# InputAnalog.net
KiCad netlist of a schematic drawn in Altium Designer
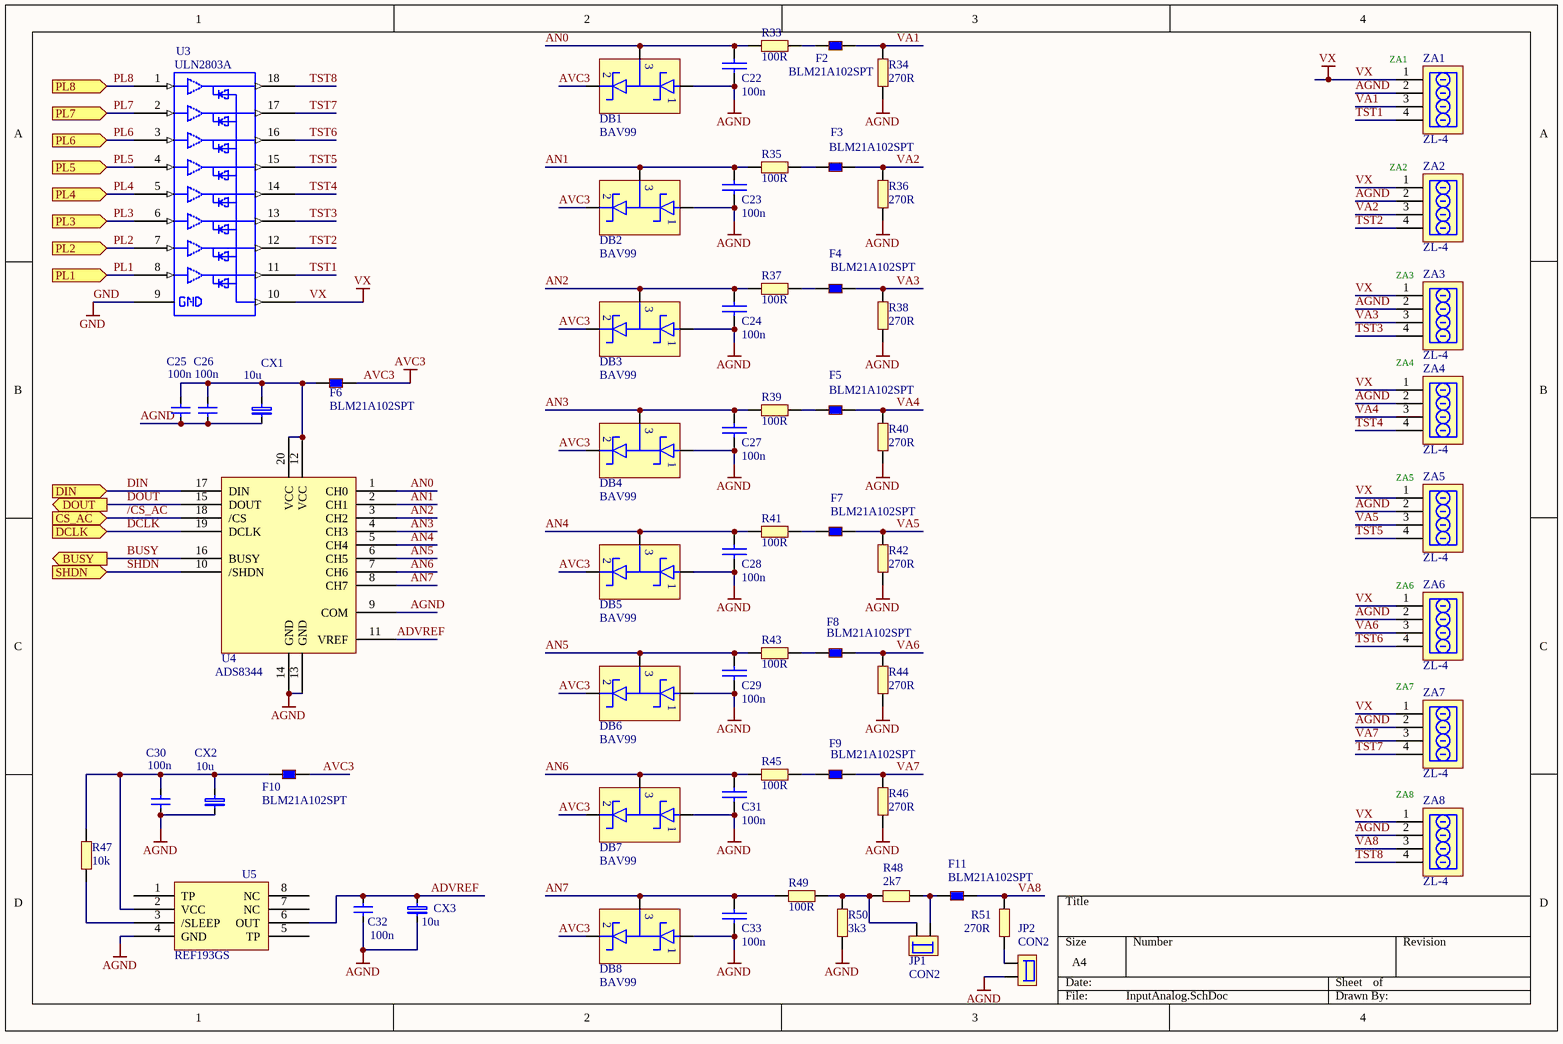
[diagram p0: InputAnalog.SchDoc]

(export (version "E")
  (design (tool "Eeschema 10.0.6"))
  (components
    (comp (ref "C22")
      (value "100n")
      (footprint "0603C")
      (description "Capacitor")
      (libsource (lib "*") (part "CAP"))
    )
    (comp (ref "C23")
      (value "100n")
      (footprint "0603C")
      (description "Capacitor")
      (libsource (lib "*") (part "CAP"))
    )
    (comp (ref "C24")
      (value "100n")
      (footprint "0603C")
      (description "Capacitor")
      (libsource (lib "*") (part "CAP"))
    )
    (comp (ref "C25") (value "100n") (footprint "0603C") (libsource (lib "") (part "CAP_1")))
    (comp (ref "C26") (value "100n") (footprint "0603C") (libsource (lib "") (part "CAP_1")))
    (comp (ref "C27")
      (value "100n")
      (footprint "0603C")
      (description "Capacitor")
      (libsource (lib "*") (part "CAP"))
    )
    (comp (ref "C28")
      (value "100n")
      (footprint "0603C")
      (description "Capacitor")
      (libsource (lib "*") (part "CAP"))
    )
    (comp (ref "C29")
      (value "100n")
      (footprint "0603C")
      (description "Capacitor")
      (libsource (lib "*") (part "CAP"))
    )
    (comp (ref "C30") (value "100n") (footprint "0603C") (libsource (lib "") (part "CAP_1")))
    (comp (ref "C31")
      (value "100n")
      (footprint "0603C")
      (description "Capacitor")
      (libsource (lib "*") (part "CAP"))
    )
    (comp (ref "C32") (value "100n") (footprint "0603C") (libsource (lib "") (part "CAP_1")))
    (comp (ref "C33")
      (value "100n")
      (footprint "0603C")
      (description "Capacitor")
      (libsource (lib "*") (part "CAP"))
    )
    (comp (ref "CX1")
      (value "10u")
      (footprint "CAP_A")
      (description "KONDENSATOR ELEKTROLITYCZNY TANTALOWY SMD")
      (libsource (lib "*") (part "CAP_TANTAL_SMD"))
    )
    (comp (ref "CX2")
      (value "10u")
      (footprint "CAP_A")
      (description "KONDENSATOR ELEKTROLITYCZNY TANTALOWY SMD")
      (libsource (lib "*") (part "CAP_TANTAL_SMD"))
    )
    (comp (ref "CX3")
      (value "10u")
      (footprint "CAP_A")
      (description "KONDENSATOR ELEKTROLITYCZNY TANTALOWY SMD")
      (libsource (lib "*") (part "CAP_TANTAL_SMD"))
    )
    (comp (ref "DB1") (value "BAV99") (footprint "SOT-23") (libsource (lib "*") (part "BAS70-04")))
    (comp (ref "DB2") (value "BAV99") (footprint "SOT-23") (libsource (lib "*") (part "BAS70-04")))
    (comp (ref "DB3") (value "BAV99") (footprint "SOT-23") (libsource (lib "*") (part "BAS70-04")))
    (comp (ref "DB4") (value "BAV99") (footprint "SOT-23") (libsource (lib "*") (part "BAS70-04")))
    (comp (ref "DB5") (value "BAV99") (footprint "SOT-23") (libsource (lib "*") (part "BAS70-04")))
    (comp (ref "DB6") (value "BAV99") (footprint "SOT-23") (libsource (lib "*") (part "BAS70-04")))
    (comp (ref "DB7") (value "BAV99") (footprint "SOT-23") (libsource (lib "*") (part "BAS70-04")))
    (comp (ref "DB8") (value "BAV99") (footprint "SOT-23") (libsource (lib "*") (part "BAS70-04")))
    (comp (ref "F2")
      (value "BLM21A102SPT")
      (footprint "0603L")
      (description "Koralik ferrytowy")
      (libsource (lib "*") (part "KORALIK"))
    )
    (comp (ref "F3")
      (value "BLM21A102SPT")
      (footprint "0603L")
      (description "Koralik ferrytowy")
      (libsource (lib "*") (part "KORALIK"))
    )
    (comp (ref "F4")
      (value "BLM21A102SPT")
      (footprint "0603L")
      (description "Koralik ferrytowy")
      (libsource (lib "*") (part "KORALIK"))
    )
    (comp (ref "F5")
      (value "BLM21A102SPT")
      (footprint "0603L")
      (description "Koralik ferrytowy")
      (libsource (lib "*") (part "KORALIK"))
    )
    (comp (ref "F6")
      (value "BLM21A102SPT")
      (footprint "0603L")
      (description "Koralik ferrytowy")
      (libsource (lib "*") (part "KORALIK"))
    )
    (comp (ref "F7")
      (value "BLM21A102SPT")
      (footprint "0603L")
      (description "Koralik ferrytowy")
      (libsource (lib "*") (part "KORALIK"))
    )
    (comp (ref "F8")
      (value "BLM21A102SPT")
      (footprint "0603L")
      (description "Koralik ferrytowy")
      (libsource (lib "*") (part "KORALIK"))
    )
    (comp (ref "F9")
      (value "BLM21A102SPT")
      (footprint "0603L")
      (description "Koralik ferrytowy")
      (libsource (lib "*") (part "KORALIK"))
    )
    (comp (ref "F10")
      (value "BLM21A102SPT")
      (footprint "0603L")
      (description "Koralik ferrytowy")
      (libsource (lib "*") (part "KORALIK"))
    )
    (comp (ref "F11")
      (value "BLM21A102SPT")
      (footprint "0603L")
      (description "Koralik ferrytowy")
      (libsource (lib "*") (part "KORALIK"))
    )
    (comp (ref "JP1")
      (value "CON2")
      (footprint "SIP2")
      (description "Connector")
      (libsource (lib "ElhosSchLib") (part "JUMP2"))
    )
    (comp (ref "JP2")
      (value "CON2")
      (footprint "SIP2")
      (description "Connector")
      (libsource (lib "") (part "JUMP2_1"))
    )
    (comp (ref "R33") (value "100R") (footprint "0603R") (libsource (lib "*") (part "RES3")))
    (comp (ref "R34") (value "270R") (footprint "0805R") (libsource (lib "") (part "RES3_1")))
    (comp (ref "R35") (value "100R") (footprint "0603R") (libsource (lib "*") (part "RES3")))
    (comp (ref "R36") (value "270R") (footprint "0805R") (libsource (lib "") (part "RES3_1")))
    (comp (ref "R37") (value "100R") (footprint "0603R") (libsource (lib "*") (part "RES3")))
    (comp (ref "R38") (value "270R") (footprint "0805R") (libsource (lib "") (part "RES3_1")))
    (comp (ref "R39") (value "100R") (footprint "0603R") (libsource (lib "*") (part "RES3")))
    (comp (ref "R40") (value "270R") (footprint "0805R") (libsource (lib "") (part "RES3_1")))
    (comp (ref "R41") (value "100R") (footprint "0603R") (libsource (lib "*") (part "RES3")))
    (comp (ref "R42") (value "270R") (footprint "0805R") (libsource (lib "") (part "RES3_1")))
    (comp (ref "R43") (value "100R") (footprint "0603R") (libsource (lib "*") (part "RES3")))
    (comp (ref "R44") (value "270R") (footprint "0805R") (libsource (lib "") (part "RES3_1")))
    (comp (ref "R45") (value "100R") (footprint "0603R") (libsource (lib "*") (part "RES3")))
    (comp (ref "R46") (value "270R") (footprint "0805R") (libsource (lib "") (part "RES3_1")))
    (comp (ref "R47") (value "10k") (footprint "0603R") (libsource (lib "*") (part "RES3")))
    (comp (ref "R48") (value "2k7") (footprint "0603R") (libsource (lib "*") (part "RES3")))
    (comp (ref "R49") (value "100R") (footprint "0603R") (libsource (lib "*") (part "RES3")))
    (comp (ref "R50") (value "3k3") (footprint "0603R") (libsource (lib "") (part "RES3_2")))
    (comp (ref "R51") (value "270R") (footprint "0805R") (libsource (lib "") (part "RES3_1")))
    (comp (ref "U3")
      (value "ULN2803A")
      (footprint "SO-18")
      (libsource (lib "*") (part "Pro31.tmp_ULN2803A_42"))
    )
    (comp (ref "U4") (value "ADS8344") (footprint "TSSOP20") (libsource (lib "*") (part "ADS8344")))
    (comp (ref "U5") (value "REF193GS") (footprint "SO8") (libsource (lib "*") (part "REF19X")))
    (comp (ref "ZA1") (value "ZL-4") (footprint "ARC-4-3.5-TYCO-2") (libsource (lib "*") (part "ZL-4")))
    (comp (ref "ZA2") (value "ZL-4") (footprint "ARC-4-3.5-TYCO-2") (libsource (lib "*") (part "ZL-4")))
    (comp (ref "ZA3") (value "ZL-4") (footprint "ARC-4-3.5-TYCO-2") (libsource (lib "*") (part "ZL-4")))
    (comp (ref "ZA4") (value "ZL-4") (footprint "ARC-4-3.5-TYCO-2") (libsource (lib "*") (part "ZL-4")))
    (comp (ref "ZA5") (value "ZL-4") (footprint "ARC-4-3.5-TYCO-2") (libsource (lib "*") (part "ZL-4")))
    (comp (ref "ZA6") (value "ZL-4") (footprint "ARC-4-3.5-TYCO-2") (libsource (lib "*") (part "ZL-4")))
    (comp (ref "ZA7") (value "ZL-4") (footprint "ARC-4-3.5-TYCO-2") (libsource (lib "*") (part "ZL-4")))
    (comp (ref "ZA8") (value "ZL-4") (footprint "ARC-4-3.5-TYCO-2") (libsource (lib "*") (part "ZL-4")))
  )
  (nets
    (net (code "1") (name "/ADVREF") (class "Default")
      (node (ref "C32") (pin "1") (pintype "passive"))
      (node (ref "CX3") (pin "2") (pintype "passive"))
      (node (ref "U4") (pin "11") (pinfunction "VREF_11") (pintype "passive"))
      (node (ref "U5") (pin "6") (pinfunction "OUT_6") (pintype "passive"))
    )
    (net (code "2") (name "/AN0") (class "Default")
      (node (ref "C22") (pin "1") (pinfunction "1_1") (pintype "passive"))
      (node (ref "DB1") (pin "3") (pintype "passive"))
      (node (ref "R33") (pin "2") (pintype "passive"))
      (node (ref "U4") (pin "1") (pinfunction "CH0_1") (pintype "passive"))
    )
    (net (code "3") (name "/AN1") (class "Default")
      (node (ref "C23") (pin "1") (pinfunction "1_1") (pintype "passive"))
      (node (ref "DB2") (pin "3") (pintype "passive"))
      (node (ref "R35") (pin "2") (pintype "passive"))
      (node (ref "U4") (pin "2") (pinfunction "CH1_2") (pintype "passive"))
    )
    (net (code "4") (name "/AN2") (class "Default")
      (node (ref "C24") (pin "1") (pinfunction "1_1") (pintype "passive"))
      (node (ref "DB3") (pin "3") (pintype "passive"))
      (node (ref "R37") (pin "2") (pintype "passive"))
      (node (ref "U4") (pin "3") (pinfunction "CH2_3") (pintype "passive"))
    )
    (net (code "5") (name "/AN3") (class "Default")
      (node (ref "C27") (pin "1") (pinfunction "1_1") (pintype "passive"))
      (node (ref "DB4") (pin "3") (pintype "passive"))
      (node (ref "R39") (pin "2") (pintype "passive"))
      (node (ref "U4") (pin "4") (pinfunction "CH3_4") (pintype "passive"))
    )
    (net (code "6") (name "/AN4") (class "Default")
      (node (ref "C28") (pin "1") (pinfunction "1_1") (pintype "passive"))
      (node (ref "DB5") (pin "3") (pintype "passive"))
      (node (ref "R41") (pin "2") (pintype "passive"))
      (node (ref "U4") (pin "5") (pinfunction "CH4_5") (pintype "passive"))
    )
    (net (code "7") (name "/AN5") (class "Default")
      (node (ref "C29") (pin "1") (pinfunction "1_1") (pintype "passive"))
      (node (ref "DB6") (pin "3") (pintype "passive"))
      (node (ref "R43") (pin "2") (pintype "passive"))
      (node (ref "U4") (pin "6") (pinfunction "CH5_6") (pintype "passive"))
    )
    (net (code "8") (name "/AN6") (class "Default")
      (node (ref "C31") (pin "1") (pinfunction "1_1") (pintype "passive"))
      (node (ref "DB7") (pin "3") (pintype "passive"))
      (node (ref "R45") (pin "2") (pintype "passive"))
      (node (ref "U4") (pin "7") (pinfunction "CH6_7") (pintype "passive"))
    )
    (net (code "9") (name "/AN7") (class "Default")
      (node (ref "C33") (pin "1") (pinfunction "1_1") (pintype "passive"))
      (node (ref "DB8") (pin "3") (pintype "passive"))
      (node (ref "R49") (pin "2") (pintype "passive"))
      (node (ref "U4") (pin "8") (pinfunction "CH7_8") (pintype "passive"))
    )
    (net (code "10") (name "/BUSY") (class "Default")
      (node (ref "U4") (pin "16") (pinfunction "BUSY_16") (pintype "passive"))
    )
    (net (code "11") (name "/DCLK") (class "Default")
      (node (ref "U4") (pin "19") (pinfunction "DCLK_19") (pintype "passive"))
    )
    (net (code "12") (name "/DIN") (class "Default")
      (node (ref "U4") (pin "17") (pinfunction "DIN_17") (pintype "passive"))
    )
    (net (code "13") (name "/DOUT") (class "Default")
      (node (ref "U4") (pin "15") (pinfunction "DOUT_15") (pintype "passive"))
    )
    (net (code "14") (name "/PL1") (class "Default") (node (ref "U3") (pin "8") (pintype "input")))
    (net (code "15") (name "/PL2") (class "Default") (node (ref "U3") (pin "7") (pintype "input")))
    (net (code "16") (name "/PL3") (class "Default") (node (ref "U3") (pin "6") (pintype "input")))
    (net (code "17") (name "/PL4") (class "Default") (node (ref "U3") (pin "5") (pintype "input")))
    (net (code "18") (name "/PL5") (class "Default") (node (ref "U3") (pin "4") (pintype "input")))
    (net (code "19") (name "/PL6") (class "Default") (node (ref "U3") (pin "3") (pintype "input")))
    (net (code "20") (name "/PL7") (class "Default") (node (ref "U3") (pin "2") (pintype "input")))
    (net (code "21") (name "/PL8") (class "Default") (node (ref "U3") (pin "1") (pintype "input")))
    (net (code "22") (name "/SHDN") (class "Default")
      (node (ref "U4") (pin "10") (pinfunction "/SHDN_10") (pintype "passive"))
    )
    (net (code "23") (name "/TST1") (class "Default")
      (node (ref "U3") (pin "11") (pintype "output"))
      (node (ref "ZA1") (pin "4") (pintype "passive"))
    )
    (net (code "24") (name "/TST2") (class "Default")
      (node (ref "U3") (pin "12") (pintype "output"))
      (node (ref "ZA2") (pin "4") (pintype "passive"))
    )
    (net (code "25") (name "/TST3") (class "Default")
      (node (ref "U3") (pin "13") (pintype "output"))
      (node (ref "ZA3") (pin "4") (pintype "passive"))
    )
    (net (code "26") (name "/TST4") (class "Default")
      (node (ref "U3") (pin "14") (pintype "output"))
      (node (ref "ZA4") (pin "4") (pintype "passive"))
    )
    (net (code "27") (name "/TST5") (class "Default")
      (node (ref "U3") (pin "15") (pintype "output"))
      (node (ref "ZA5") (pin "4") (pintype "passive"))
    )
    (net (code "28") (name "/TST6") (class "Default")
      (node (ref "U3") (pin "16") (pintype "output"))
      (node (ref "ZA6") (pin "4") (pintype "passive"))
    )
    (net (code "29") (name "/TST7") (class "Default")
      (node (ref "U3") (pin "17") (pintype "output"))
      (node (ref "ZA7") (pin "4") (pintype "passive"))
    )
    (net (code "30") (name "/TST8") (class "Default")
      (node (ref "U3") (pin "18") (pintype "output"))
      (node (ref "ZA8") (pin "4") (pintype "passive"))
    )
    (net (code "31") (name "/VA1") (class "Default")
      (node (ref "F2") (pin "2") (pintype "passive"))
      (node (ref "R34") (pin "2") (pintype "passive"))
      (node (ref "ZA1") (pin "3") (pintype "passive"))
    )
    (net (code "32") (name "/VA2") (class "Default")
      (node (ref "F3") (pin "2") (pintype "passive"))
      (node (ref "R36") (pin "2") (pintype "passive"))
      (node (ref "ZA2") (pin "3") (pintype "passive"))
    )
    (net (code "33") (name "/VA3") (class "Default")
      (node (ref "F4") (pin "2") (pintype "passive"))
      (node (ref "R38") (pin "2") (pintype "passive"))
      (node (ref "ZA3") (pin "3") (pintype "passive"))
    )
    (net (code "34") (name "/VA4") (class "Default")
      (node (ref "F5") (pin "2") (pintype "passive"))
      (node (ref "R40") (pin "2") (pintype "passive"))
      (node (ref "ZA4") (pin "3") (pintype "passive"))
    )
    (net (code "35") (name "/VA5") (class "Default")
      (node (ref "F7") (pin "2") (pintype "passive"))
      (node (ref "R42") (pin "2") (pintype "passive"))
      (node (ref "ZA5") (pin "3") (pintype "passive"))
    )
    (net (code "36") (name "/VA6") (class "Default")
      (node (ref "F8") (pin "2") (pintype "passive"))
      (node (ref "R44") (pin "2") (pintype "passive"))
      (node (ref "ZA6") (pin "3") (pintype "passive"))
    )
    (net (code "37") (name "/VA7") (class "Default")
      (node (ref "F9") (pin "2") (pintype "passive"))
      (node (ref "R46") (pin "2") (pintype "passive"))
      (node (ref "ZA7") (pin "3") (pintype "passive"))
    )
    (net (code "38") (name "/VA8") (class "Default")
      (node (ref "F11") (pin "2") (pintype "passive"))
      (node (ref "R51") (pin "2") (pintype "passive"))
      (node (ref "ZA8") (pin "3") (pintype "passive"))
    )
    (net (code "39") (name "/{slash}CS_AC") (class "Default")
      (node (ref "U4") (pin "18") (pinfunction "/CS_18") (pintype "passive"))
    )
    (net (code "40") (name "AGND") (class "Default")
      (node (ref "C22") (pin "2") (pinfunction "2_2") (pintype "passive"))
      (node (ref "C23") (pin "2") (pinfunction "2_2") (pintype "passive"))
      (node (ref "C24") (pin "2") (pinfunction "2_2") (pintype "passive"))
      (node (ref "C25") (pin "2") (pintype "passive"))
      (node (ref "C26") (pin "2") (pintype "passive"))
      (node (ref "C27") (pin "2") (pinfunction "2_2") (pintype "passive"))
      (node (ref "C28") (pin "2") (pinfunction "2_2") (pintype "passive"))
      (node (ref "C29") (pin "2") (pinfunction "2_2") (pintype "passive"))
      (node (ref "C30") (pin "2") (pintype "passive"))
      (node (ref "C31") (pin "2") (pinfunction "2_2") (pintype "passive"))
      (node (ref "C32") (pin "2") (pintype "passive"))
      (node (ref "C33") (pin "2") (pinfunction "2_2") (pintype "passive"))
      (node (ref "CX1") (pin "1") (pintype "passive"))
      (node (ref "CX2") (pin "1") (pintype "passive"))
      (node (ref "CX3") (pin "1") (pintype "passive"))
      (node (ref "DB1") (pin "1") (pintype "passive"))
      (node (ref "DB2") (pin "1") (pintype "passive"))
      (node (ref "DB3") (pin "1") (pintype "passive"))
      (node (ref "DB4") (pin "1") (pintype "passive"))
      (node (ref "DB5") (pin "1") (pintype "passive"))
      (node (ref "DB6") (pin "1") (pintype "passive"))
      (node (ref "DB7") (pin "1") (pintype "passive"))
      (node (ref "DB8") (pin "1") (pintype "passive"))
      (node (ref "JP2") (pin "2") (pinfunction "2_2") (pintype "passive"))
      (node (ref "R34") (pin "1") (pintype "passive"))
      (node (ref "R36") (pin "1") (pintype "passive"))
      (node (ref "R38") (pin "1") (pintype "passive"))
      (node (ref "R40") (pin "1") (pintype "passive"))
      (node (ref "R42") (pin "1") (pintype "passive"))
      (node (ref "R44") (pin "1") (pintype "passive"))
      (node (ref "R46") (pin "1") (pintype "passive"))
      (node (ref "R50") (pin "2") (pintype "passive"))
      (node (ref "U4") (pin "13") (pinfunction "GND_13") (pintype "passive"))
      (node (ref "U4") (pin "14") (pinfunction "GND_14") (pintype "passive"))
      (node (ref "U4") (pin "9") (pinfunction "COM_9") (pintype "passive"))
      (node (ref "U5") (pin "4") (pinfunction "GND_4") (pintype "passive"))
      (node (ref "ZA1") (pin "2") (pintype "passive"))
      (node (ref "ZA2") (pin "2") (pintype "passive"))
      (node (ref "ZA3") (pin "2") (pintype "passive"))
      (node (ref "ZA4") (pin "2") (pintype "passive"))
      (node (ref "ZA5") (pin "2") (pintype "passive"))
      (node (ref "ZA6") (pin "2") (pintype "passive"))
      (node (ref "ZA7") (pin "2") (pintype "passive"))
      (node (ref "ZA8") (pin "2") (pintype "passive"))
    )
    (net (code "41") (name "AVC3") (class "Default")
      (node (ref "DB1") (pin "2") (pintype "passive"))
      (node (ref "DB2") (pin "2") (pintype "passive"))
      (node (ref "DB3") (pin "2") (pintype "passive"))
      (node (ref "DB4") (pin "2") (pintype "passive"))
      (node (ref "DB5") (pin "2") (pintype "passive"))
      (node (ref "DB6") (pin "2") (pintype "passive"))
      (node (ref "DB7") (pin "2") (pintype "passive"))
      (node (ref "DB8") (pin "2") (pintype "passive"))
      (node (ref "F10") (pin "2") (pintype "passive"))
      (node (ref "F6") (pin "2") (pintype "passive"))
    )
    (net (code "42") (name "GND") (class "Default") (node (ref "U3") (pin "9") (pintype "passive")))
    (net (code "43") (name "Net-(C25-Pad1)") (class "Default")
      (node (ref "C25") (pin "1") (pintype "passive"))
      (node (ref "C26") (pin "1") (pintype "passive"))
      (node (ref "CX1") (pin "2") (pintype "passive"))
      (node (ref "F6") (pin "1") (pintype "passive"))
      (node (ref "U4") (pin "12") (pinfunction "VCC_12") (pintype "passive"))
      (node (ref "U4") (pin "20") (pinfunction "VCC_20") (pintype "passive"))
    )
    (net (code "44") (name "Net-(F2-Pad1)") (class "Default")
      (node (ref "F2") (pin "1") (pintype "passive"))
      (node (ref "R33") (pin "1") (pintype "passive"))
    )
    (net (code "45") (name "Net-(F3-Pad1)") (class "Default")
      (node (ref "F3") (pin "1") (pintype "passive"))
      (node (ref "R35") (pin "1") (pintype "passive"))
    )
    (net (code "46") (name "Net-(F4-Pad1)") (class "Default")
      (node (ref "F4") (pin "1") (pintype "passive"))
      (node (ref "R37") (pin "1") (pintype "passive"))
    )
    (net (code "47") (name "Net-(F5-Pad1)") (class "Default")
      (node (ref "F5") (pin "1") (pintype "passive"))
      (node (ref "R39") (pin "1") (pintype "passive"))
    )
    (net (code "48") (name "Net-(F7-Pad1)") (class "Default")
      (node (ref "F7") (pin "1") (pintype "passive"))
      (node (ref "R41") (pin "1") (pintype "passive"))
    )
    (net (code "49") (name "Net-(F8-Pad1)") (class "Default")
      (node (ref "F8") (pin "1") (pintype "passive"))
      (node (ref "R43") (pin "1") (pintype "passive"))
    )
    (net (code "50") (name "Net-(F9-Pad1)") (class "Default")
      (node (ref "F9") (pin "1") (pintype "passive"))
      (node (ref "R45") (pin "1") (pintype "passive"))
    )
    (net (code "51") (name "Net-(F11-Pad1)") (class "Default")
      (node (ref "F11") (pin "1") (pintype "passive"))
      (node (ref "JP1") (pin "1") (pinfunction "1_1") (pintype "passive"))
      (node (ref "R48") (pin "1") (pintype "passive"))
    )
    (net (code "52") (name "Net-(JP1-Pad2)") (class "Default")
      (node (ref "JP1") (pin "2") (pinfunction "2_2") (pintype "passive"))
      (node (ref "R48") (pin "2") (pintype "passive"))
      (node (ref "R49") (pin "1") (pintype "passive"))
      (node (ref "R50") (pin "1") (pintype "passive"))
    )
    (net (code "53") (name "Net-(JP2-Pad1)") (class "Default")
      (node (ref "JP2") (pin "1") (pinfunction "1_1") (pintype "passive"))
      (node (ref "R51") (pin "1") (pintype "passive"))
    )
    (net (code "54") (name "Net-(U5-VCC)") (class "Default")
      (node (ref "C30") (pin "1") (pintype "passive"))
      (node (ref "CX2") (pin "2") (pintype "passive"))
      (node (ref "F10") (pin "1") (pintype "passive"))
      (node (ref "R47") (pin "1") (pintype "passive"))
      (node (ref "U5") (pin "2") (pinfunction "VCC_2") (pintype "passive"))
    )
    (net (code "55") (name "Net-(U5-{slash}SLEEP)") (class "Default")
      (node (ref "R47") (pin "2") (pintype "passive"))
      (node (ref "U5") (pin "3") (pinfunction "/SLEEP_3") (pintype "passive"))
    )
    (net (code "56") (name "VX") (class "Default")
      (node (ref "U3") (pin "10") (pintype "output"))
      (node (ref "ZA1") (pin "1") (pintype "passive"))
      (node (ref "ZA2") (pin "1") (pintype "passive"))
      (node (ref "ZA3") (pin "1") (pintype "passive"))
      (node (ref "ZA4") (pin "1") (pintype "passive"))
      (node (ref "ZA5") (pin "1") (pintype "passive"))
      (node (ref "ZA6") (pin "1") (pintype "passive"))
      (node (ref "ZA7") (pin "1") (pintype "passive"))
      (node (ref "ZA8") (pin "1") (pintype "passive"))
    )
    (net (code "57") (name "unconnected-(U5-NC-Pad7)") (class "Default")
      (node (ref "U5") (pin "7") (pinfunction "NC_7") (pintype "passive"))
    )
    (net (code "58") (name "unconnected-(U5-NC-Pad8)") (class "Default")
      (node (ref "U5") (pin "8") (pinfunction "NC_8") (pintype "passive"))
    )
    (net (code "59") (name "unconnected-(U5-TP-Pad1)") (class "Default")
      (node (ref "U5") (pin "1") (pinfunction "TP_1") (pintype "passive"))
    )
    (net (code "60") (name "unconnected-(U5-TP-Pad5)") (class "Default")
      (node (ref "U5") (pin "5") (pinfunction "TP_5") (pintype "passive"))
    )
  )
)
